# MicroMultimeter_USB_Sch.net
KiCad netlist of a schematic drawn in Altium Designer
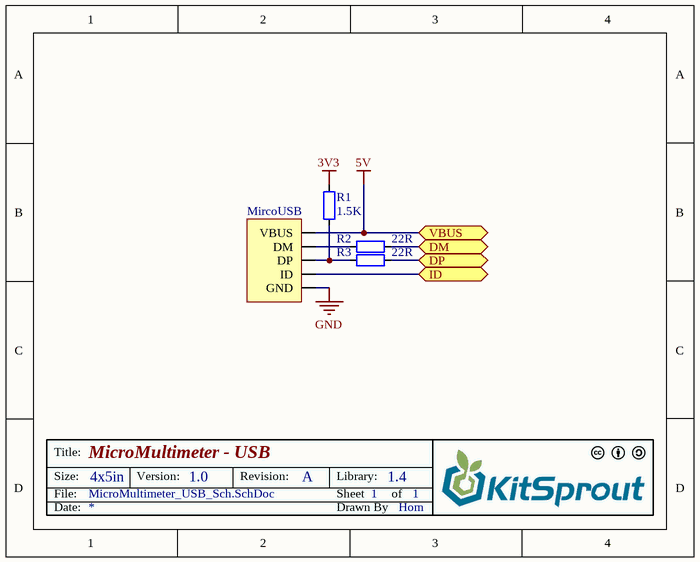
[diagram p0: MicroMultimeter_USB_Sch.SchDoc]

(export (version "E")
  (design (tool "Eeschema 10.0.6"))
  (components
    (comp (ref "MircoUSB")
      (value "USB_Micro")
      (footprint "PCB_USB:USB_Micro-AB")
      (description "USB")
      (libsource (lib "SCH_USB") (part "USB_Micro"))
    )
    (comp (ref "R1")
      (value "1.5K")
      (footprint "RES_0603")
      (description "Resistor")
      (fields (field (name "Comment") "Res_0603"))
      (libsource (lib "") (part "Res_0603_1"))
    )
    (comp (ref "R2")
      (value "22R")
      (footprint "RES_0603")
      (description "Resistor")
      (fields (field (name "Comment") "Res_0603"))
      (libsource (lib "SCH_Passive") (part "Res_0603"))
    )
    (comp (ref "R3")
      (value "22R")
      (footprint "RES_0603")
      (description "Resistor")
      (fields (field (name "Comment") "Res_0603"))
      (libsource (lib "SCH_Passive") (part "Res_0603"))
    )
  )
  (nets
    (net (code "1") (name "/DM") (class "Default")
      (node (ref "R2") (pin "2") (pinfunction "2_2") (pintype "passive"))
    )
    (net (code "2") (name "/DP") (class "Default")
      (node (ref "R3") (pin "2") (pinfunction "2_2") (pintype "passive"))
    )
    (net (code "3") (name "/ID") (class "Default")
      (node (ref "MircoUSB") (pin "4") (pinfunction "ID_4") (pintype "passive"))
    )
    (net (code "4") (name "3V3") (class "Default")
      (node (ref "R1") (pin "1") (pinfunction "1_1") (pintype "passive"))
    )
    (net (code "5") (name "5V") (class "Default")
      (node (ref "MircoUSB") (pin "1") (pinfunction "VBUS_1") (pintype "passive"))
    )
    (net (code "6") (name "GND") (class "Default")
      (node (ref "MircoUSB") (pin "5") (pinfunction "GND_5") (pintype "passive"))
    )
    (net (code "7") (name "Net-(MircoUSB-DM)") (class "Default")
      (node (ref "MircoUSB") (pin "2") (pinfunction "DM_2") (pintype "passive"))
      (node (ref "R2") (pin "1") (pinfunction "1_1") (pintype "passive"))
    )
    (net (code "8") (name "Net-(MircoUSB-DP)") (class "Default")
      (node (ref "MircoUSB") (pin "3") (pinfunction "DP_3") (pintype "passive"))
      (node (ref "R1") (pin "2") (pinfunction "2_2") (pintype "passive"))
      (node (ref "R3") (pin "1") (pinfunction "1_1") (pintype "passive"))
    )
  )
)
